# pca20054_sheet3_antenna_switches.net
KiCad netlist of a schematic drawn in Altium Designer
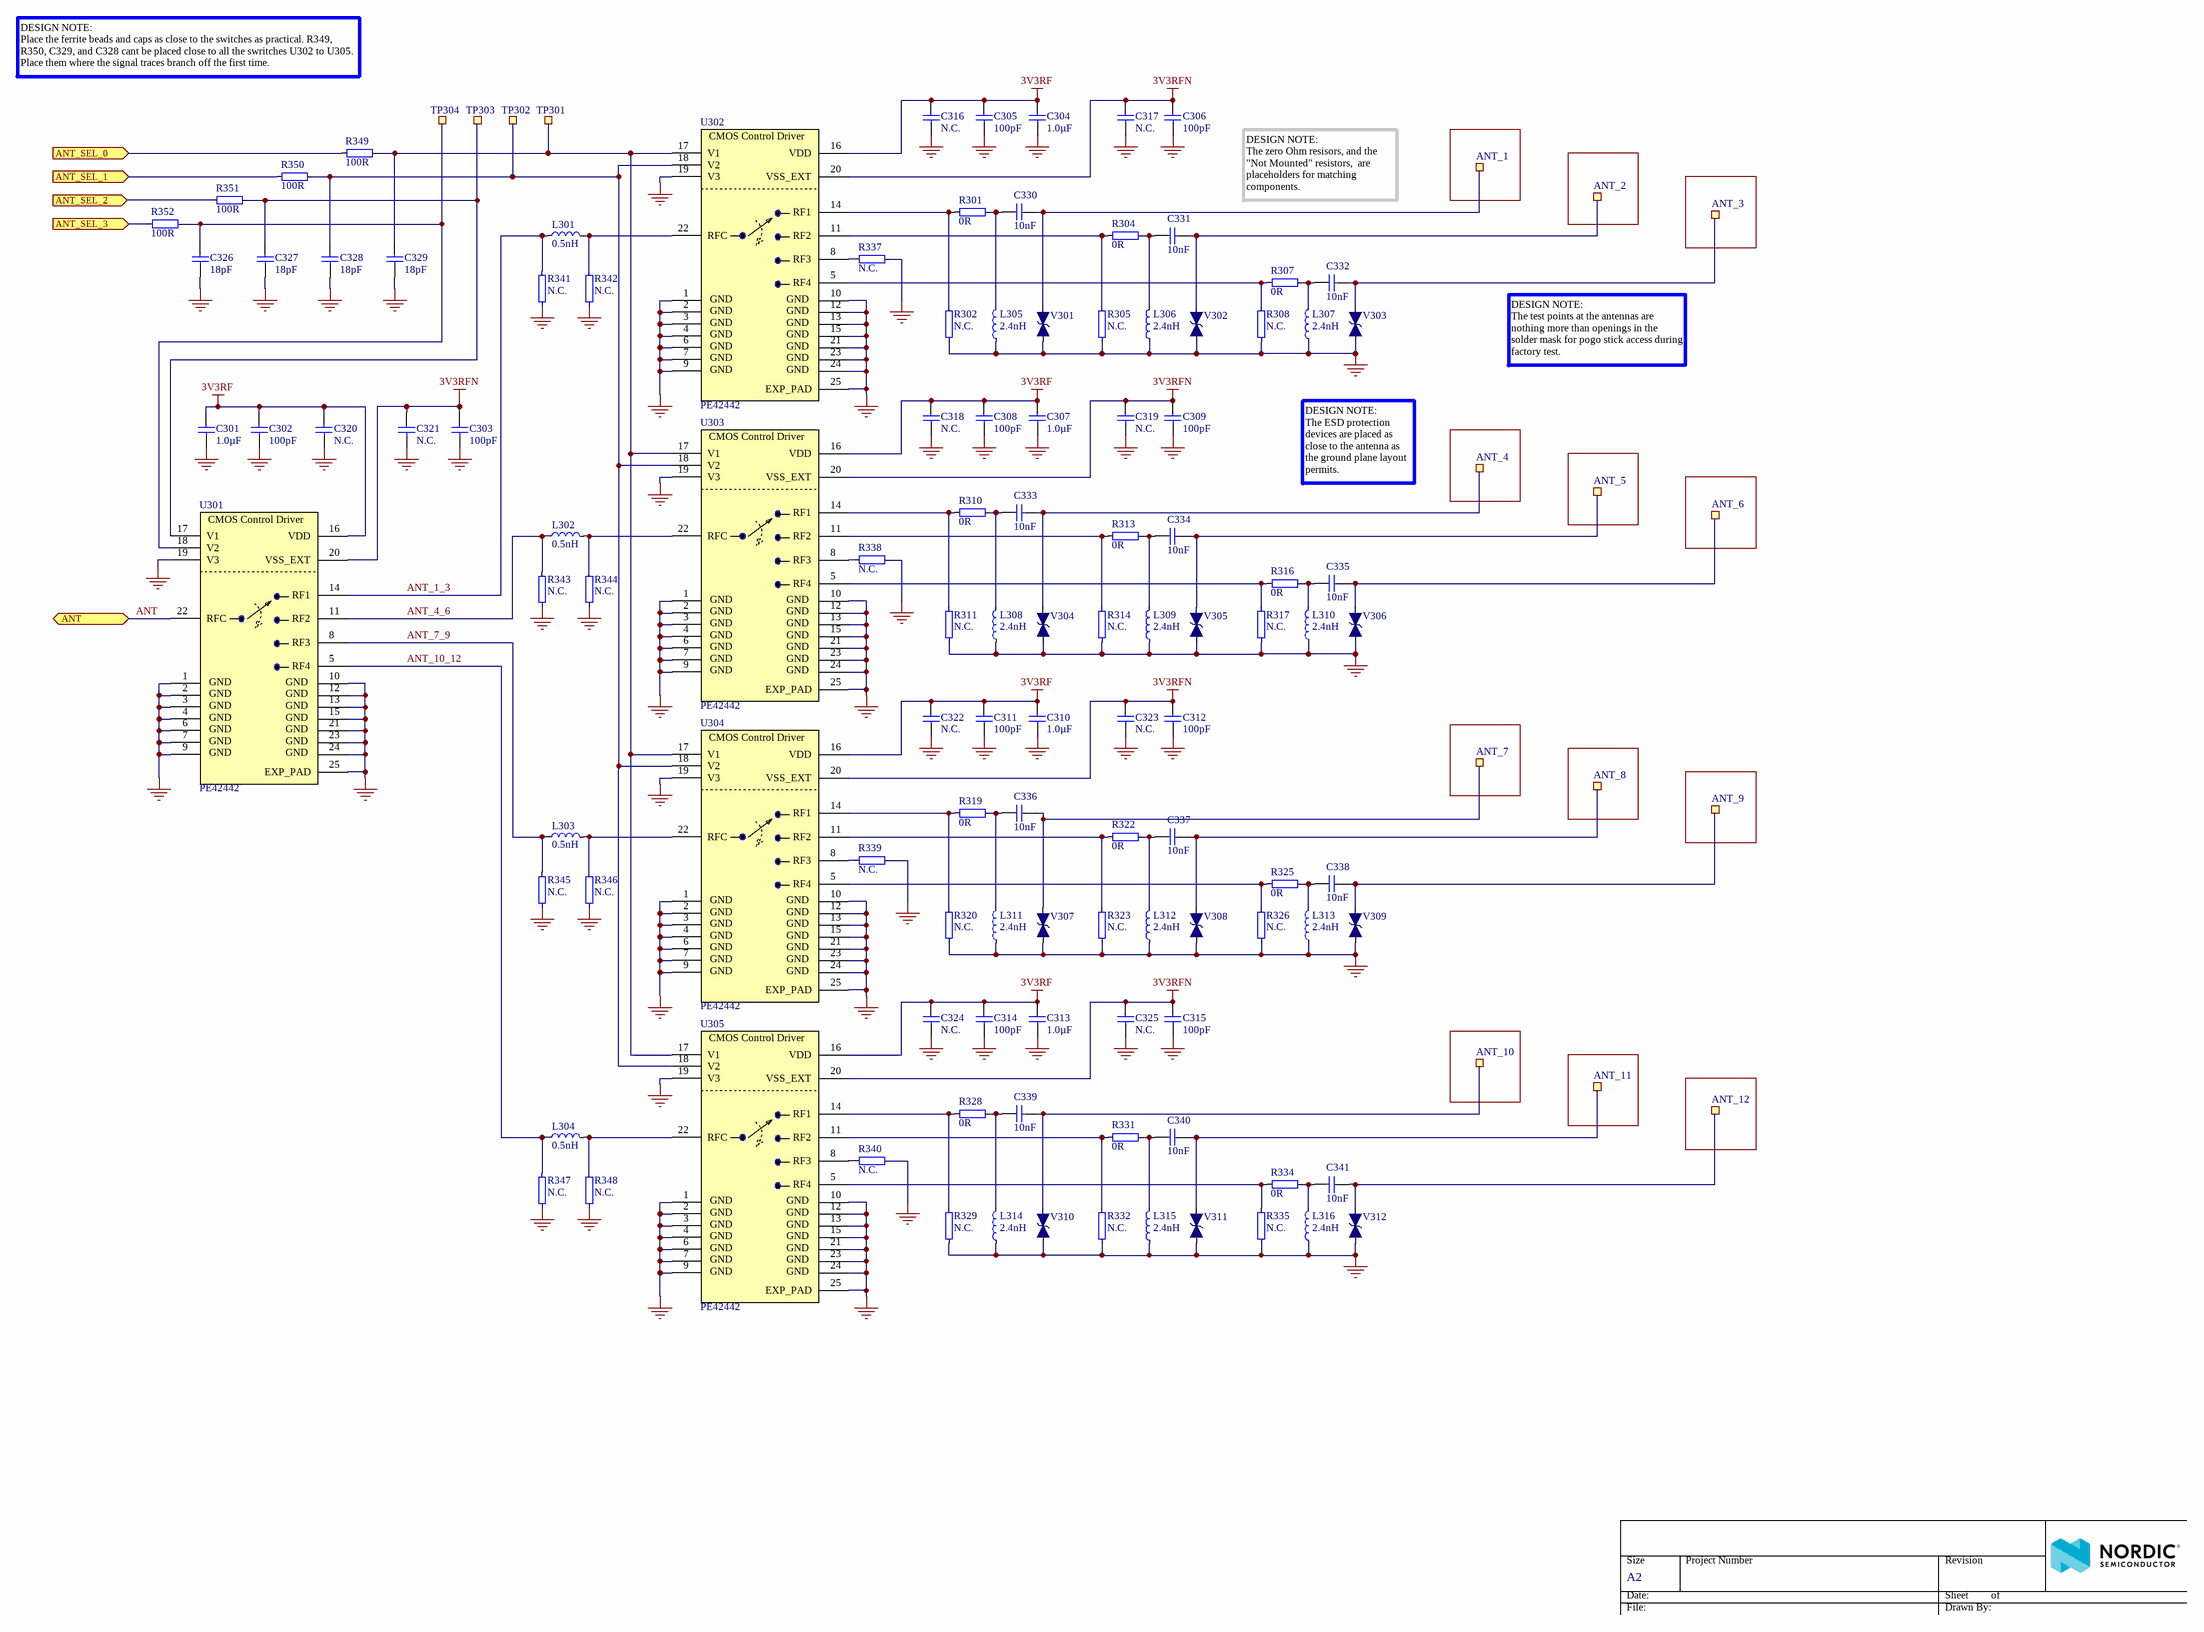
[diagram p0: pca20054_sheet3_antenna_switches.SchDoc]

(export (version "E")
  (design (tool "Eeschema 10.0.6"))
  (components
    (comp (ref "ANT_1")
      (value "Ø1.0mm,SMD")
      (footprint "TP_SMD_Ø1.0mm")
      (description "1.0mm circular SMD testpad")
      (fields
        (field (name "PART NUMBER") "TP_SMD_Ø1.0MM")
        (field (name "MANUFACTURER") "Nordic Semiconductor")
        (field (name "PUBLISHER") "Nordic Semiconductor")
      )
      (libsource (lib "Nordic Passive DB") (part "TESTPAD"))
    )
    (comp (ref "ANT_2")
      (value "Ø1.0mm,SMD")
      (footprint "TP_SMD_Ø1.0mm")
      (description "1.0mm circular SMD testpad")
      (fields
        (field (name "PART NUMBER") "TP_SMD_Ø1.0MM")
        (field (name "MANUFACTURER") "Nordic Semiconductor")
        (field (name "PUBLISHER") "Nordic Semiconductor")
      )
      (libsource (lib "Nordic Passive DB") (part "TESTPAD"))
    )
    (comp (ref "ANT_3")
      (value "Ø1.0mm,SMD")
      (footprint "TP_SMD_Ø1.0mm")
      (description "1.0mm circular SMD testpad")
      (fields
        (field (name "PART NUMBER") "TP_SMD_Ø1.0MM")
        (field (name "MANUFACTURER") "Nordic Semiconductor")
        (field (name "PUBLISHER") "Nordic Semiconductor")
      )
      (libsource (lib "Nordic Passive DB") (part "TESTPAD"))
    )
    (comp (ref "ANT_4")
      (value "Ø1.0mm,SMD")
      (footprint "TP_SMD_Ø1.0mm")
      (description "1.0mm circular SMD testpad")
      (fields
        (field (name "PART NUMBER") "TP_SMD_Ø1.0MM")
        (field (name "MANUFACTURER") "Nordic Semiconductor")
        (field (name "PUBLISHER") "Nordic Semiconductor")
      )
      (libsource (lib "Nordic Passive DB") (part "TESTPAD"))
    )
    (comp (ref "ANT_5")
      (value "Ø1.0mm,SMD")
      (footprint "TP_SMD_Ø1.0mm")
      (description "1.0mm circular SMD testpad")
      (fields
        (field (name "PART NUMBER") "TP_SMD_Ø1.0MM")
        (field (name "MANUFACTURER") "Nordic Semiconductor")
        (field (name "PUBLISHER") "Nordic Semiconductor")
      )
      (libsource (lib "Nordic Passive DB") (part "TESTPAD"))
    )
    (comp (ref "ANT_6")
      (value "Ø1.0mm,SMD")
      (footprint "TP_SMD_Ø1.0mm")
      (description "1.0mm circular SMD testpad")
      (fields
        (field (name "PART NUMBER") "TP_SMD_Ø1.0MM")
        (field (name "MANUFACTURER") "Nordic Semiconductor")
        (field (name "PUBLISHER") "Nordic Semiconductor")
      )
      (libsource (lib "Nordic Passive DB") (part "TESTPAD"))
    )
    (comp (ref "ANT_7")
      (value "Ø1.0mm,SMD")
      (footprint "TP_SMD_Ø1.0mm")
      (description "1.0mm circular SMD testpad")
      (fields
        (field (name "PART NUMBER") "TP_SMD_Ø1.0MM")
        (field (name "MANUFACTURER") "Nordic Semiconductor")
        (field (name "PUBLISHER") "Nordic Semiconductor")
      )
      (libsource (lib "Nordic Passive DB") (part "TESTPAD"))
    )
    (comp (ref "ANT_8")
      (value "Ø1.0mm,SMD")
      (footprint "TP_SMD_Ø1.0mm")
      (description "1.0mm circular SMD testpad")
      (fields
        (field (name "PART NUMBER") "TP_SMD_Ø1.0MM")
        (field (name "MANUFACTURER") "Nordic Semiconductor")
        (field (name "PUBLISHER") "Nordic Semiconductor")
      )
      (libsource (lib "Nordic Passive DB") (part "TESTPAD"))
    )
    (comp (ref "ANT_9")
      (value "Ø1.0mm,SMD")
      (footprint "TP_SMD_Ø1.0mm")
      (description "1.0mm circular SMD testpad")
      (fields
        (field (name "PART NUMBER") "TP_SMD_Ø1.0MM")
        (field (name "MANUFACTURER") "Nordic Semiconductor")
        (field (name "PUBLISHER") "Nordic Semiconductor")
      )
      (libsource (lib "Nordic Passive DB") (part "TESTPAD"))
    )
    (comp (ref "ANT_10")
      (value "Ø1.0mm,SMD")
      (footprint "TP_SMD_Ø1.0mm")
      (description "1.0mm circular SMD testpad")
      (fields
        (field (name "PART NUMBER") "TP_SMD_Ø1.0MM")
        (field (name "MANUFACTURER") "Nordic Semiconductor")
        (field (name "PUBLISHER") "Nordic Semiconductor")
      )
      (libsource (lib "Nordic Passive DB") (part "TESTPAD"))
    )
    (comp (ref "ANT_11")
      (value "Ø1.0mm,SMD")
      (footprint "TP_SMD_Ø1.0mm")
      (description "1.0mm circular SMD testpad")
      (fields
        (field (name "PART NUMBER") "TP_SMD_Ø1.0MM")
        (field (name "MANUFACTURER") "Nordic Semiconductor")
        (field (name "PUBLISHER") "Nordic Semiconductor")
      )
      (libsource (lib "Nordic Passive DB") (part "TESTPAD"))
    )
    (comp (ref "ANT_12")
      (value "Ø1.0mm,SMD")
      (footprint "TP_SMD_Ø1.0mm")
      (description "1.0mm circular SMD testpad")
      (fields
        (field (name "PART NUMBER") "TP_SMD_Ø1.0MM")
        (field (name "MANUFACTURER") "Nordic Semiconductor")
        (field (name "PUBLISHER") "Nordic Semiconductor")
      )
      (libsource (lib "Nordic Passive DB") (part "TESTPAD"))
    )
    (comp (ref "C301")
      (value "1.0µF")
      (footprint "CAPC1608X06L")
      (description "Capacitor, X7R, ±10%")
      (fields (field (name "PART NUMBER") "C0603-1µ0") (field (name "PUBLISHER") "Nordic Semiconductor"))
      (libsource (lib "Nordic Passive DB") (part "CAP"))
    )
    (comp (ref "C302")
      (value "100pF")
      (footprint "CAPC1005X04L")
      (description "Capacitor, NP0, ±5%")
      (fields (field (name "PART NUMBER") "C0402-100p") (field (name "PUBLISHER") "Nordic Semiconductor"))
      (libsource (lib "Nordic Passive DB") (part "CAP"))
    )
    (comp (ref "C303")
      (value "100pF")
      (footprint "CAPC1005X04L")
      (description "Capacitor, NP0, ±5%")
      (fields (field (name "PART NUMBER") "C0402-100p") (field (name "PUBLISHER") "Nordic Semiconductor"))
      (libsource (lib "Nordic Passive DB") (part "CAP"))
    )
    (comp (ref "C304")
      (value "1.0µF")
      (footprint "CAPC1608X06L")
      (description "Capacitor, X7R, ±10%")
      (fields (field (name "PART NUMBER") "C0603-1µ0") (field (name "PUBLISHER") "Nordic Semiconductor"))
      (libsource (lib "Nordic Passive DB") (part "CAP"))
    )
    (comp (ref "C305")
      (value "100pF")
      (footprint "CAPC1005X04L")
      (description "Capacitor, NP0, ±5%")
      (fields (field (name "PART NUMBER") "C0402-100p") (field (name "PUBLISHER") "Nordic Semiconductor"))
      (libsource (lib "Nordic Passive DB") (part "CAP"))
    )
    (comp (ref "C306")
      (value "100pF")
      (footprint "CAPC1005X04L")
      (description "Capacitor, NP0, ±5%")
      (fields (field (name "PART NUMBER") "C0402-100p") (field (name "PUBLISHER") "Nordic Semiconductor"))
      (libsource (lib "Nordic Passive DB") (part "CAP"))
    )
    (comp (ref "C307")
      (value "1.0µF")
      (footprint "CAPC1608X06L")
      (description "Capacitor, X7R, ±10%")
      (fields (field (name "PART NUMBER") "C0603-1µ0") (field (name "PUBLISHER") "Nordic Semiconductor"))
      (libsource (lib "Nordic Passive DB") (part "CAP"))
    )
    (comp (ref "C308")
      (value "100pF")
      (footprint "CAPC1005X04L")
      (description "Capacitor, NP0, ±5%")
      (fields (field (name "PART NUMBER") "C0402-100p") (field (name "PUBLISHER") "Nordic Semiconductor"))
      (libsource (lib "Nordic Passive DB") (part "CAP"))
    )
    (comp (ref "C309")
      (value "100pF")
      (footprint "CAPC1005X04L")
      (description "Capacitor, NP0, ±5%")
      (fields (field (name "PART NUMBER") "C0402-100p") (field (name "PUBLISHER") "Nordic Semiconductor"))
      (libsource (lib "Nordic Passive DB") (part "CAP"))
    )
    (comp (ref "C310")
      (value "1.0µF")
      (footprint "CAPC1608X06L")
      (description "Capacitor, X7R, ±10%")
      (fields (field (name "PART NUMBER") "C0603-1µ0") (field (name "PUBLISHER") "Nordic Semiconductor"))
      (libsource (lib "Nordic Passive DB") (part "CAP"))
    )
    (comp (ref "C311")
      (value "100pF")
      (footprint "CAPC1005X04L")
      (description "Capacitor, NP0, ±5%")
      (fields (field (name "PART NUMBER") "C0402-100p") (field (name "PUBLISHER") "Nordic Semiconductor"))
      (libsource (lib "Nordic Passive DB") (part "CAP"))
    )
    (comp (ref "C312")
      (value "100pF")
      (footprint "CAPC1005X04L")
      (description "Capacitor, NP0, ±5%")
      (fields (field (name "PART NUMBER") "C0402-100p") (field (name "PUBLISHER") "Nordic Semiconductor"))
      (libsource (lib "Nordic Passive DB") (part "CAP"))
    )
    (comp (ref "C313")
      (value "1.0µF")
      (footprint "CAPC1608X06L")
      (description "Capacitor, X7R, ±10%")
      (fields (field (name "PART NUMBER") "C0603-1µ0") (field (name "PUBLISHER") "Nordic Semiconductor"))
      (libsource (lib "Nordic Passive DB") (part "CAP"))
    )
    (comp (ref "C314")
      (value "100pF")
      (footprint "CAPC1005X04L")
      (description "Capacitor, NP0, ±5%")
      (fields (field (name "PART NUMBER") "C0402-100p") (field (name "PUBLISHER") "Nordic Semiconductor"))
      (libsource (lib "Nordic Passive DB") (part "CAP"))
    )
    (comp (ref "C315")
      (value "100pF")
      (footprint "CAPC1005X04L")
      (description "Capacitor, NP0, ±5%")
      (fields (field (name "PART NUMBER") "C0402-100p") (field (name "PUBLISHER") "Nordic Semiconductor"))
      (libsource (lib "Nordic Passive DB") (part "CAP"))
    )
    (comp (ref "C316")
      (value "N.C.")
      (footprint "CAPC1005X04L_NC")
      (description "Not mounted")
      (fields (field (name "PART NUMBER") "C0402-N.C.") (field (name "PUBLISHER") "Nordic Semiconductor"))
      (libsource (lib "Nordic Passive DB") (part "CAP"))
    )
    (comp (ref "C317")
      (value "N.C.")
      (footprint "CAPC1005X04L_NC")
      (description "Not mounted")
      (fields (field (name "PART NUMBER") "C0402-N.C.") (field (name "PUBLISHER") "Nordic Semiconductor"))
      (libsource (lib "Nordic Passive DB") (part "CAP"))
    )
    (comp (ref "C318")
      (value "N.C.")
      (footprint "CAPC1005X04L_NC")
      (description "Not mounted")
      (fields (field (name "PART NUMBER") "C0402-N.C.") (field (name "PUBLISHER") "Nordic Semiconductor"))
      (libsource (lib "Nordic Passive DB") (part "CAP"))
    )
    (comp (ref "C319")
      (value "N.C.")
      (footprint "CAPC1005X04L_NC")
      (description "Not mounted")
      (fields (field (name "PART NUMBER") "C0402-N.C.") (field (name "PUBLISHER") "Nordic Semiconductor"))
      (libsource (lib "Nordic Passive DB") (part "CAP"))
    )
    (comp (ref "C320")
      (value "N.C.")
      (footprint "CAPC1005X04L_NC")
      (description "Not mounted")
      (fields (field (name "PART NUMBER") "C0402-N.C.") (field (name "PUBLISHER") "Nordic Semiconductor"))
      (libsource (lib "Nordic Passive DB") (part "CAP"))
    )
    (comp (ref "C321")
      (value "N.C.")
      (footprint "CAPC1005X04L_NC")
      (description "Not mounted")
      (fields (field (name "PART NUMBER") "C0402-N.C.") (field (name "PUBLISHER") "Nordic Semiconductor"))
      (libsource (lib "Nordic Passive DB") (part "CAP"))
    )
    (comp (ref "C322")
      (value "N.C.")
      (footprint "CAPC1005X04L_NC")
      (description "Not mounted")
      (fields (field (name "PART NUMBER") "C0402-N.C.") (field (name "PUBLISHER") "Nordic Semiconductor"))
      (libsource (lib "Nordic Passive DB") (part "CAP"))
    )
    (comp (ref "C323")
      (value "N.C.")
      (footprint "CAPC1005X04L_NC")
      (description "Not mounted")
      (fields (field (name "PART NUMBER") "C0402-N.C.") (field (name "PUBLISHER") "Nordic Semiconductor"))
      (libsource (lib "Nordic Passive DB") (part "CAP"))
    )
    (comp (ref "C324")
      (value "N.C.")
      (footprint "CAPC1005X04L_NC")
      (description "Not mounted")
      (fields (field (name "PART NUMBER") "C0402-N.C.") (field (name "PUBLISHER") "Nordic Semiconductor"))
      (libsource (lib "Nordic Passive DB") (part "CAP"))
    )
    (comp (ref "C325")
      (value "N.C.")
      (footprint "CAPC1005X04L_NC")
      (description "Not mounted")
      (fields (field (name "PART NUMBER") "C0402-N.C.") (field (name "PUBLISHER") "Nordic Semiconductor"))
      (libsource (lib "Nordic Passive DB") (part "CAP"))
    )
    (comp (ref "C326")
      (value "18pF")
      (footprint "CAPC1005X04L")
      (description "Capacitor, NP0, ±5%")
      (fields (field (name "PART NUMBER") "C0402-18p") (field (name "PUBLISHER") "Nordic Semiconductor"))
      (libsource (lib "Nordic Passive DB") (part "CAP"))
    )
    (comp (ref "C327")
      (value "18pF")
      (footprint "CAPC1005X04L")
      (description "Capacitor, NP0, ±5%")
      (fields (field (name "PART NUMBER") "C0402-18p") (field (name "PUBLISHER") "Nordic Semiconductor"))
      (libsource (lib "Nordic Passive DB") (part "CAP"))
    )
    (comp (ref "C328")
      (value "18pF")
      (footprint "CAPC1005X04L")
      (description "Capacitor, NP0, ±5%")
      (fields (field (name "PART NUMBER") "C0402-18p") (field (name "PUBLISHER") "Nordic Semiconductor"))
      (libsource (lib "Nordic Passive DB") (part "CAP"))
    )
    (comp (ref "C329")
      (value "18pF")
      (footprint "CAPC1005X04L")
      (description "Capacitor, NP0, ±5%")
      (fields (field (name "PART NUMBER") "C0402-18p") (field (name "PUBLISHER") "Nordic Semiconductor"))
      (libsource (lib "Nordic Passive DB") (part "CAP"))
    )
    (comp (ref "C330")
      (value "10nF")
      (footprint "CAPC1005X04L")
      (description "Capacitor, X7R, ±10%")
      (fields (field (name "PART NUMBER") "C0402-10n") (field (name "PUBLISHER") "Nordic Semiconductor"))
      (libsource (lib "Nordic Passive DB") (part "CAP"))
    )
    (comp (ref "C331")
      (value "10nF")
      (footprint "CAPC1005X04L")
      (description "Capacitor, X7R, ±10%")
      (fields (field (name "PART NUMBER") "C0402-10n") (field (name "PUBLISHER") "Nordic Semiconductor"))
      (libsource (lib "Nordic Passive DB") (part "CAP"))
    )
    (comp (ref "C332")
      (value "10nF")
      (footprint "CAPC1005X04L")
      (description "Capacitor, X7R, ±10%")
      (fields (field (name "PART NUMBER") "C0402-10n") (field (name "PUBLISHER") "Nordic Semiconductor"))
      (libsource (lib "Nordic Passive DB") (part "CAP"))
    )
    (comp (ref "C333")
      (value "10nF")
      (footprint "CAPC1005X04L")
      (description "Capacitor, X7R, ±10%")
      (fields (field (name "PART NUMBER") "C0402-10n") (field (name "PUBLISHER") "Nordic Semiconductor"))
      (libsource (lib "Nordic Passive DB") (part "CAP"))
    )
    (comp (ref "C334")
      (value "10nF")
      (footprint "CAPC1005X04L")
      (description "Capacitor, X7R, ±10%")
      (fields (field (name "PART NUMBER") "C0402-10n") (field (name "PUBLISHER") "Nordic Semiconductor"))
      (libsource (lib "Nordic Passive DB") (part "CAP"))
    )
    (comp (ref "C335")
      (value "10nF")
      (footprint "CAPC1005X04L")
      (description "Capacitor, X7R, ±10%")
      (fields (field (name "PART NUMBER") "C0402-10n") (field (name "PUBLISHER") "Nordic Semiconductor"))
      (libsource (lib "Nordic Passive DB") (part "CAP"))
    )
    (comp (ref "C336")
      (value "10nF")
      (footprint "CAPC1005X04L")
      (description "Capacitor, X7R, ±10%")
      (fields (field (name "PART NUMBER") "C0402-10n") (field (name "PUBLISHER") "Nordic Semiconductor"))
      (libsource (lib "Nordic Passive DB") (part "CAP"))
    )
    (comp (ref "C337")
      (value "10nF")
      (footprint "CAPC1005X04L")
      (description "Capacitor, X7R, ±10%")
      (fields (field (name "PART NUMBER") "C0402-10n") (field (name "PUBLISHER") "Nordic Semiconductor"))
      (libsource (lib "Nordic Passive DB") (part "CAP"))
    )
    (comp (ref "C338")
      (value "10nF")
      (footprint "CAPC1005X04L")
      (description "Capacitor, X7R, ±10%")
      (fields (field (name "PART NUMBER") "C0402-10n") (field (name "PUBLISHER") "Nordic Semiconductor"))
      (libsource (lib "Nordic Passive DB") (part "CAP"))
    )
    (comp (ref "C339")
      (value "10nF")
      (footprint "CAPC1005X04L")
      (description "Capacitor, X7R, ±10%")
      (fields (field (name "PART NUMBER") "C0402-10n") (field (name "PUBLISHER") "Nordic Semiconductor"))
      (libsource (lib "Nordic Passive DB") (part "CAP"))
    )
    (comp (ref "C340")
      (value "10nF")
      (footprint "CAPC1005X04L")
      (description "Capacitor, X7R, ±10%")
      (fields (field (name "PART NUMBER") "C0402-10n") (field (name "PUBLISHER") "Nordic Semiconductor"))
      (libsource (lib "Nordic Passive DB") (part "CAP"))
    )
    (comp (ref "C341")
      (value "10nF")
      (footprint "CAPC1005X04L")
      (description "Capacitor, X7R, ±10%")
      (fields (field (name "PART NUMBER") "C0402-10n") (field (name "PUBLISHER") "Nordic Semiconductor"))
      (libsource (lib "Nordic Passive DB") (part "CAP"))
    )
    (comp (ref "L301")
      (value "0.5nH")
      (footprint "INDC1005X04L")
      (description "Inductor, 1A, ±0.1nH")
      (fields
        (field (name "PART NUMBER") "L0402-0n5")
        (field (name "MANUFACTURER") "TDK Corporation")
        (field (name "PUBLISHER") "Nordic Semiconductor")
      )
      (libsource (lib "Nordic Passive DB") (part "IND"))
    )
    (comp (ref "L302")
      (value "0.5nH")
      (footprint "INDC1005X04L")
      (description "Inductor, 1A, ±0.1nH")
      (fields
        (field (name "PART NUMBER") "L0402-0n5")
        (field (name "MANUFACTURER") "TDK Corporation")
        (field (name "PUBLISHER") "Nordic Semiconductor")
      )
      (libsource (lib "Nordic Passive DB") (part "IND"))
    )
    (comp (ref "L303")
      (value "0.5nH")
      (footprint "INDC1005X04L")
      (description "Inductor, 1A, ±0.1nH")
      (fields
        (field (name "PART NUMBER") "L0402-0n5")
        (field (name "MANUFACTURER") "TDK Corporation")
        (field (name "PUBLISHER") "Nordic Semiconductor")
      )
      (libsource (lib "Nordic Passive DB") (part "IND"))
    )
    (comp (ref "L304")
      (value "0.5nH")
      (footprint "INDC1005X04L")
      (description "Inductor, 1A, ±0.1nH")
      (fields
        (field (name "PART NUMBER") "L0402-0n5")
        (field (name "MANUFACTURER") "TDK Corporation")
        (field (name "PUBLISHER") "Nordic Semiconductor")
      )
      (libsource (lib "Nordic Passive DB") (part "IND"))
    )
    (comp (ref "L305")
      (value "2.4nH")
      (footprint "INDC1005X04L")
      (description "Inductor, 220mA, ±0.1nH")
      (fields (field (name "PART NUMBER") "L0402-2n4") (field (name "PUBLISHER") "Nordic Semiconductor"))
      (libsource (lib "Nordic Passive DB") (part "IND"))
    )
    (comp (ref "L306")
      (value "2.4nH")
      (footprint "INDC1005X04L")
      (description "Inductor, 220mA, ±0.1nH")
      (fields (field (name "PART NUMBER") "L0402-2n4") (field (name "PUBLISHER") "Nordic Semiconductor"))
      (libsource (lib "Nordic Passive DB") (part "IND"))
    )
    (comp (ref "L307")
      (value "2.4nH")
      (footprint "INDC1005X04L")
      (description "Inductor, 220mA, ±0.1nH")
      (fields (field (name "PART NUMBER") "L0402-2n4") (field (name "PUBLISHER") "Nordic Semiconductor"))
      (libsource (lib "Nordic Passive DB") (part "IND"))
    )
    (comp (ref "L308")
      (value "2.4nH")
      (footprint "INDC1005X04L")
      (description "Inductor, 220mA, ±0.1nH")
      (fields (field (name "PART NUMBER") "L0402-2n4") (field (name "PUBLISHER") "Nordic Semiconductor"))
      (libsource (lib "Nordic Passive DB") (part "IND"))
    )
    (comp (ref "L309")
      (value "2.4nH")
      (footprint "INDC1005X04L")
      (description "Inductor, 220mA, ±0.1nH")
      (fields (field (name "PART NUMBER") "L0402-2n4") (field (name "PUBLISHER") "Nordic Semiconductor"))
      (libsource (lib "Nordic Passive DB") (part "IND"))
    )
    (comp (ref "L310")
      (value "2.4nH")
      (footprint "INDC1005X04L")
      (description "Inductor, 220mA, ±0.1nH")
      (fields (field (name "PART NUMBER") "L0402-2n4") (field (name "PUBLISHER") "Nordic Semiconductor"))
      (libsource (lib "Nordic Passive DB") (part "IND"))
    )
    (comp (ref "L311")
      (value "2.4nH")
      (footprint "INDC1005X04L")
      (description "Inductor, 220mA, ±0.1nH")
      (fields (field (name "PART NUMBER") "L0402-2n4") (field (name "PUBLISHER") "Nordic Semiconductor"))
      (libsource (lib "Nordic Passive DB") (part "IND"))
    )
    (comp (ref "L312")
      (value "2.4nH")
      (footprint "INDC1005X04L")
      (description "Inductor, 220mA, ±0.1nH")
      (fields (field (name "PART NUMBER") "L0402-2n4") (field (name "PUBLISHER") "Nordic Semiconductor"))
      (libsource (lib "Nordic Passive DB") (part "IND"))
    )
    (comp (ref "L313")
      (value "2.4nH")
      (footprint "INDC1005X04L")
      (description "Inductor, 220mA, ±0.1nH")
      (fields (field (name "PART NUMBER") "L0402-2n4") (field (name "PUBLISHER") "Nordic Semiconductor"))
      (libsource (lib "Nordic Passive DB") (part "IND"))
    )
    (comp (ref "L314")
      (value "2.4nH")
      (footprint "INDC1005X04L")
      (description "Inductor, 220mA, ±0.1nH")
      (fields (field (name "PART NUMBER") "L0402-2n4") (field (name "PUBLISHER") "Nordic Semiconductor"))
      (libsource (lib "Nordic Passive DB") (part "IND"))
    )
    (comp (ref "L315")
      (value "2.4nH")
      (footprint "INDC1005X04L")
      (description "Inductor, 220mA, ±0.1nH")
      (fields (field (name "PART NUMBER") "L0402-2n4") (field (name "PUBLISHER") "Nordic Semiconductor"))
      (libsource (lib "Nordic Passive DB") (part "IND"))
    )
    (comp (ref "L316")
      (value "2.4nH")
      (footprint "INDC1005X04L")
      (description "Inductor, 220mA, ±0.1nH")
      (fields (field (name "PART NUMBER") "L0402-2n4") (field (name "PUBLISHER") "Nordic Semiconductor"))
      (libsource (lib "Nordic Passive DB") (part "IND"))
    )
    (comp (ref "R301")
      (value "0R")
      (footprint "RESC1005X04L")
      (description "Resistor, ±5%, 0.063W")
      (fields (field (name "PART NUMBER") "R0402-0R") (field (name "PUBLISHER") "Nordic Semiconductor"))
      (libsource (lib "Nordic Passive DB") (part "RES"))
    )
    (comp (ref "R302")
      (value "N.C.")
      (footprint "RESC1005X04L_NC")
      (description "Not mounted")
      (fields (field (name "PART NUMBER") "R0402-N.C.") (field (name "PUBLISHER") "Nordic Semiconductor"))
      (libsource (lib "Nordic Passive DB") (part "RES"))
    )
    (comp (ref "R304")
      (value "0R")
      (footprint "RESC1005X04L")
      (description "Resistor, ±5%, 0.063W")
      (fields (field (name "PART NUMBER") "R0402-0R") (field (name "PUBLISHER") "Nordic Semiconductor"))
      (libsource (lib "Nordic Passive DB") (part "RES"))
    )
    (comp (ref "R305")
      (value "N.C.")
      (footprint "RESC1005X04L_NC")
      (description "Not mounted")
      (fields (field (name "PART NUMBER") "R0402-N.C.") (field (name "PUBLISHER") "Nordic Semiconductor"))
      (libsource (lib "Nordic Passive DB") (part "RES"))
    )
    (comp (ref "R307")
      (value "0R")
      (footprint "RESC1005X04L")
      (description "Resistor, ±5%, 0.063W")
      (fields (field (name "PART NUMBER") "R0402-0R") (field (name "PUBLISHER") "Nordic Semiconductor"))
      (libsource (lib "Nordic Passive DB") (part "RES"))
    )
    (comp (ref "R308")
      (value "N.C.")
      (footprint "RESC1005X04L_NC")
      (description "Not mounted")
      (fields (field (name "PART NUMBER") "R0402-N.C.") (field (name "PUBLISHER") "Nordic Semiconductor"))
      (libsource (lib "Nordic Passive DB") (part "RES"))
    )
    (comp (ref "R310")
      (value "0R")
      (footprint "RESC1005X04L")
      (description "Resistor, ±5%, 0.063W")
      (fields (field (name "PART NUMBER") "R0402-0R") (field (name "PUBLISHER") "Nordic Semiconductor"))
      (libsource (lib "Nordic Passive DB") (part "RES"))
    )
    (comp (ref "R311")
      (value "N.C.")
      (footprint "RESC1005X04L_NC")
      (description "Not mounted")
      (fields (field (name "PART NUMBER") "R0402-N.C.") (field (name "PUBLISHER") "Nordic Semiconductor"))
      (libsource (lib "Nordic Passive DB") (part "RES"))
    )
    (comp (ref "R313")
      (value "0R")
      (footprint "RESC1005X04L")
      (description "Resistor, ±5%, 0.063W")
      (fields (field (name "PART NUMBER") "R0402-0R") (field (name "PUBLISHER") "Nordic Semiconductor"))
      (libsource (lib "Nordic Passive DB") (part "RES"))
    )
    (comp (ref "R314")
      (value "N.C.")
      (footprint "RESC1005X04L_NC")
      (description "Not mounted")
      (fields (field (name "PART NUMBER") "R0402-N.C.") (field (name "PUBLISHER") "Nordic Semiconductor"))
      (libsource (lib "Nordic Passive DB") (part "RES"))
    )
    (comp (ref "R316")
      (value "0R")
      (footprint "RESC1005X04L")
      (description "Resistor, ±5%, 0.063W")
      (fields (field (name "PART NUMBER") "R0402-0R") (field (name "PUBLISHER") "Nordic Semiconductor"))
      (libsource (lib "Nordic Passive DB") (part "RES"))
    )
    (comp (ref "R317")
      (value "N.C.")
      (footprint "RESC1005X04L_NC")
      (description "Not mounted")
      (fields (field (name "PART NUMBER") "R0402-N.C.") (field (name "PUBLISHER") "Nordic Semiconductor"))
      (libsource (lib "Nordic Passive DB") (part "RES"))
    )
    (comp (ref "R319")
      (value "0R")
      (footprint "RESC1005X04L")
      (description "Resistor, ±5%, 0.063W")
      (fields (field (name "PART NUMBER") "R0402-0R") (field (name "PUBLISHER") "Nordic Semiconductor"))
      (libsource (lib "Nordic Passive DB") (part "RES"))
    )
    (comp (ref "R320")
      (value "N.C.")
      (footprint "RESC1005X04L_NC")
      (description "Not mounted")
      (fields (field (name "PART NUMBER") "R0402-N.C.") (field (name "PUBLISHER") "Nordic Semiconductor"))
      (libsource (lib "Nordic Passive DB") (part "RES"))
    )
    (comp (ref "R322")
      (value "0R")
      (footprint "RESC1005X04L")
      (description "Resistor, ±5%, 0.063W")
      (fields (field (name "PART NUMBER") "R0402-0R") (field (name "PUBLISHER") "Nordic Semiconductor"))
      (libsource (lib "Nordic Passive DB") (part "RES"))
    )
    (comp (ref "R323")
      (value "N.C.")
      (footprint "RESC1005X04L_NC")
      (description "Not mounted")
      (fields (field (name "PART NUMBER") "R0402-N.C.") (field (name "PUBLISHER") "Nordic Semiconductor"))
      (libsource (lib "Nordic Passive DB") (part "RES"))
    )
    (comp (ref "R325")
      (value "0R")
      (footprint "RESC1005X04L")
      (description "Resistor, ±5%, 0.063W")
      (fields (field (name "PART NUMBER") "R0402-0R") (field (name "PUBLISHER") "Nordic Semiconductor"))
      (libsource (lib "Nordic Passive DB") (part "RES"))
    )
    (comp (ref "R326")
      (value "N.C.")
      (footprint "RESC1005X04L_NC")
      (description "Not mounted")
      (fields (field (name "PART NUMBER") "R0402-N.C.") (field (name "PUBLISHER") "Nordic Semiconductor"))
      (libsource (lib "Nordic Passive DB") (part "RES"))
    )
    (comp (ref "R328")
      (value "0R")
      (footprint "RESC1005X04L")
      (description "Resistor, ±5%, 0.063W")
      (fields (field (name "PART NUMBER") "R0402-0R") (field (name "PUBLISHER") "Nordic Semiconductor"))
      (libsource (lib "Nordic Passive DB") (part "RES"))
    )
    (comp (ref "R329")
      (value "N.C.")
      (footprint "RESC1005X04L_NC")
      (description "Not mounted")
      (fields (field (name "PART NUMBER") "R0402-N.C.") (field (name "PUBLISHER") "Nordic Semiconductor"))
      (libsource (lib "Nordic Passive DB") (part "RES"))
    )
    (comp (ref "R331")
      (value "0R")
      (footprint "RESC1005X04L")
      (description "Resistor, ±5%, 0.063W")
      (fields (field (name "PART NUMBER") "R0402-0R") (field (name "PUBLISHER") "Nordic Semiconductor"))
      (libsource (lib "Nordic Passive DB") (part "RES"))
    )
    (comp (ref "R332")
      (value "N.C.")
      (footprint "RESC1005X04L_NC")
      (description "Not mounted")
      (fields (field (name "PART NUMBER") "R0402-N.C.") (field (name "PUBLISHER") "Nordic Semiconductor"))
      (libsource (lib "Nordic Passive DB") (part "RES"))
    )
    (comp (ref "R334")
      (value "0R")
      (footprint "RESC1005X04L")
      (description "Resistor, ±5%, 0.063W")
      (fields (field (name "PART NUMBER") "R0402-0R") (field (name "PUBLISHER") "Nordic Semiconductor"))
      (libsource (lib "Nordic Passive DB") (part "RES"))
    )
    (comp (ref "R335")
      (value "N.C.")
      (footprint "RESC1005X04L_NC")
      (description "Not mounted")
      (fields (field (name "PART NUMBER") "R0402-N.C.") (field (name "PUBLISHER") "Nordic Semiconductor"))
      (libsource (lib "Nordic Passive DB") (part "RES"))
    )
    (comp (ref "R337")
      (value "N.C.")
      (footprint "RESC1005X04L_NC")
      (description "Not mounted")
      (fields (field (name "PART NUMBER") "R0402-N.C.") (field (name "PUBLISHER") "Nordic Semiconductor"))
      (libsource (lib "Nordic Passive DB") (part "RES"))
    )
    (comp (ref "R338")
      (value "N.C.")
      (footprint "RESC1005X04L_NC")
      (description "Not mounted")
      (fields (field (name "PART NUMBER") "R0402-N.C.") (field (name "PUBLISHER") "Nordic Semiconductor"))
      (libsource (lib "Nordic Passive DB") (part "RES"))
    )
    (comp (ref "R339")
      (value "N.C.")
      (footprint "RESC1005X04L_NC")
      (description "Not mounted")
      (fields (field (name "PART NUMBER") "R0402-N.C.") (field (name "PUBLISHER") "Nordic Semiconductor"))
      (libsource (lib "Nordic Passive DB") (part "RES"))
    )
    (comp (ref "R340")
      (value "N.C.")
      (footprint "RESC1005X04L_NC")
      (description "Not mounted")
      (fields (field (name "PART NUMBER") "R0402-N.C.") (field (name "PUBLISHER") "Nordic Semiconductor"))
      (libsource (lib "Nordic Passive DB") (part "RES"))
    )
    (comp (ref "R341")
      (value "N.C.")
      (footprint "RESC1005X04L_NC")
      (description "Not mounted")
      (fields (field (name "PART NUMBER") "R0402-N.C.") (field (name "PUBLISHER") "Nordic Semiconductor"))
      (libsource (lib "Nordic Passive DB") (part "RES"))
    )
    (comp (ref "R342")
      (value "N.C.")
      (footprint "RESC1005X04L_NC")
      (description "Not mounted")
      (fields (field (name "PART NUMBER") "R0402-N.C.") (field (name "PUBLISHER") "Nordic Semiconductor"))
      (libsource (lib "Nordic Passive DB") (part "RES"))
    )
    (comp (ref "R343")
      (value "N.C.")
      (footprint "RESC1005X04L_NC")
      (description "Not mounted")
      (fields (field (name "PART NUMBER") "R0402-N.C.") (field (name "PUBLISHER") "Nordic Semiconductor"))
      (libsource (lib "Nordic Passive DB") (part "RES"))
    )
    (comp (ref "R344")
      (value "N.C.")
      (footprint "RESC1005X04L_NC")
      (description "Not mounted")
      (fields (field (name "PART NUMBER") "R0402-N.C.") (field (name "PUBLISHER") "Nordic Semiconductor"))
      (libsource (lib "Nordic Passive DB") (part "RES"))
    )
    (comp (ref "R345")
      (value "N.C.")
      (footprint "RESC1005X04L_NC")
      (description "Not mounted")
      (fields (field (name "PART NUMBER") "R0402-N.C.") (field (name "PUBLISHER") "Nordic Semiconductor"))
      (libsource (lib "Nordic Passive DB") (part "RES"))
    )
    (comp (ref "R346")
      (value "N.C.")
      (footprint "RESC1005X04L_NC")
      (description "Not mounted")
      (fields (field (name "PART NUMBER") "R0402-N.C.") (field (name "PUBLISHER") "Nordic Semiconductor"))
      (libsource (lib "Nordic Passive DB") (part "RES"))
    )
    (comp (ref "R347")
      (value "N.C.")
      (footprint "RESC1005X04L_NC")
      (description "Not mounted")
      (fields (field (name "PART NUMBER") "R0402-N.C.") (field (name "PUBLISHER") "Nordic Semiconductor"))
      (libsource (lib "Nordic Passive DB") (part "RES"))
    )
    (comp (ref "R348")
      (value "N.C.")
      (footprint "RESC1005X04L_NC")
      (description "Not mounted")
      (fields (field (name "PART NUMBER") "R0402-N.C.") (field (name "PUBLISHER") "Nordic Semiconductor"))
      (libsource (lib "Nordic Passive DB") (part "RES"))
    )
    (comp (ref "R349")
      (value "100R")
      (footprint "RESC1005X04L")
      (description "Resistor, ±1%, 0.063W")
      (fields (field (name "PART NUMBER") "R0402-100") (field (name "PUBLISHER") "Nordic Semiconductor"))
      (libsource (lib "Nordic Passive DB") (part "RES"))
    )
    (comp (ref "R350")
      (value "100R")
      (footprint "RESC1005X04L")
      (description "Resistor, ±1%, 0.063W")
      (fields (field (name "PART NUMBER") "R0402-100") (field (name "PUBLISHER") "Nordic Semiconductor"))
      (libsource (lib "Nordic Passive DB") (part "RES"))
    )
    (comp (ref "R351")
      (value "100R")
      (footprint "RESC1005X04L")
      (description "Resistor, ±1%, 0.063W")
      (fields (field (name "PART NUMBER") "R0402-100") (field (name "PUBLISHER") "Nordic Semiconductor"))
      (libsource (lib "Nordic Passive DB") (part "RES"))
    )
    (comp (ref "R352")
      (value "100R")
      (footprint "RESC1005X04L")
      (description "Resistor, ±1%, 0.063W")
      (fields (field (name "PART NUMBER") "R0402-100") (field (name "PUBLISHER") "Nordic Semiconductor"))
      (libsource (lib "Nordic Passive DB") (part "RES"))
    )
    (comp (ref "TP301")
      (value "Ø1.0mm,SMD")
      (footprint "TP_SMD_Ø1.0mm")
      (description "1.0mm circular SMD testpad")
      (fields
        (field (name "PART NUMBER") "TP_SMD_Ø1.0MM")
        (field (name "MANUFACTURER") "Nordic Semiconductor")
        (field (name "PUBLISHER") "Nordic Semiconductor")
      )
      (libsource (lib "Nordic Passive DB") (part "TESTPAD"))
    )
    (comp (ref "TP302")
      (value "Ø1.0mm,SMD")
      (footprint "TP_SMD_Ø1.0mm")
      (description "1.0mm circular SMD testpad")
      (fields
        (field (name "PART NUMBER") "TP_SMD_Ø1.0MM")
        (field (name "MANUFACTURER") "Nordic Semiconductor")
        (field (name "PUBLISHER") "Nordic Semiconductor")
      )
      (libsource (lib "Nordic Passive DB") (part "TESTPAD"))
    )
    (comp (ref "TP303")
      (value "Ø1.0mm,SMD")
      (footprint "TP_SMD_Ø1.0mm")
      (description "1.0mm circular SMD testpad")
      (fields
        (field (name "PART NUMBER") "TP_SMD_Ø1.0MM")
        (field (name "MANUFACTURER") "Nordic Semiconductor")
        (field (name "PUBLISHER") "Nordic Semiconductor")
      )
      (libsource (lib "Nordic Passive DB") (part "TESTPAD"))
    )
    (comp (ref "TP304")
      (value "Ø1.0mm,SMD")
      (footprint "TP_SMD_Ø1.0mm")
      (description "1.0mm circular SMD testpad")
      (fields
        (field (name "PART NUMBER") "TP_SMD_Ø1.0MM")
        (field (name "MANUFACTURER") "Nordic Semiconductor")
        (field (name "PUBLISHER") "Nordic Semiconductor")
      )
      (libsource (lib "Nordic Passive DB") (part "TESTPAD"))
    )
    (comp (ref "U301")
      (value "PE42442")
      (footprint "QFN50P400X400X80_HS-25N")
      (description "UltraCMOS SP4T RF Switch 30 MHz-6 GHz")
      (fields
        (field (name "MANUFACTURER") "Peregrine Semiconductors")
        (field (name "PUBLISHER") "Nordic Semiconductor")
      )
      (libsource (lib "Nordic Active DB") (part "PE42442"))
    )
    (comp (ref "U302")
      (value "PE42442")
      (footprint "QFN50P400X400X80_HS-25N")
      (description "UltraCMOS SP4T RF Switch 30 MHz-6 GHz")
      (fields
        (field (name "MANUFACTURER") "Peregrine Semiconductors")
        (field (name "PUBLISHER") "Nordic Semiconductor")
      )
      (libsource (lib "Nordic Active DB") (part "PE42442"))
    )
    (comp (ref "U303")
      (value "PE42442")
      (footprint "QFN50P400X400X80_HS-25N")
      (description "UltraCMOS SP4T RF Switch 30 MHz-6 GHz")
      (fields
        (field (name "MANUFACTURER") "Peregrine Semiconductors")
        (field (name "PUBLISHER") "Nordic Semiconductor")
      )
      (libsource (lib "Nordic Active DB") (part "PE42442"))
    )
    (comp (ref "U304")
      (value "PE42442")
      (footprint "QFN50P400X400X80_HS-25N")
      (description "UltraCMOS SP4T RF Switch 30 MHz-6 GHz")
      (fields
        (field (name "MANUFACTURER") "Peregrine Semiconductors")
        (field (name "PUBLISHER") "Nordic Semiconductor")
      )
      (libsource (lib "Nordic Active DB") (part "PE42442"))
    )
    (comp (ref "U305")
      (value "PE42442")
      (footprint "QFN50P400X400X80_HS-25N")
      (description "UltraCMOS SP4T RF Switch 30 MHz-6 GHz")
      (fields
        (field (name "MANUFACTURER") "Peregrine Semiconductors")
        (field (name "PUBLISHER") "Nordic Semiconductor")
      )
      (libsource (lib "Nordic Active DB") (part "PE42442"))
    )
    (comp (ref "V301")
      (value "LXES15AAA1-133")
      (footprint "RESC1005X04L")
      (description "TVS DIODE 15VWM 0402")
      (fields (field (name "MANUFACTURER") "Murata") (field (name "PUBLISHER") "Nordic Semiconductor"))
      (libsource (lib "Nordic Discrete DB") (part "D{colon}SUPP"))
    )
    (comp (ref "V302")
      (value "LXES15AAA1-133")
      (footprint "RESC1005X04L")
      (description "TVS DIODE 15VWM 0402")
      (fields (field (name "MANUFACTURER") "Murata") (field (name "PUBLISHER") "Nordic Semiconductor"))
      (libsource (lib "Nordic Discrete DB") (part "D{colon}SUPP"))
    )
    (comp (ref "V303")
      (value "LXES15AAA1-133")
      (footprint "RESC1005X04L")
      (description "TVS DIODE 15VWM 0402")
      (fields (field (name "MANUFACTURER") "Murata") (field (name "PUBLISHER") "Nordic Semiconductor"))
      (libsource (lib "Nordic Discrete DB") (part "D{colon}SUPP"))
    )
    (comp (ref "V304")
      (value "LXES15AAA1-133")
      (footprint "RESC1005X04L")
      (description "TVS DIODE 15VWM 0402")
      (fields (field (name "MANUFACTURER") "Murata") (field (name "PUBLISHER") "Nordic Semiconductor"))
      (libsource (lib "Nordic Discrete DB") (part "D{colon}SUPP"))
    )
    (comp (ref "V305")
      (value "LXES15AAA1-133")
      (footprint "RESC1005X04L")
      (description "TVS DIODE 15VWM 0402")
      (fields (field (name "MANUFACTURER") "Murata") (field (name "PUBLISHER") "Nordic Semiconductor"))
      (libsource (lib "Nordic Discrete DB") (part "D{colon}SUPP"))
    )
    (comp (ref "V306")
      (value "LXES15AAA1-133")
      (footprint "RESC1005X04L")
      (description "TVS DIODE 15VWM 0402")
      (fields (field (name "MANUFACTURER") "Murata") (field (name "PUBLISHER") "Nordic Semiconductor"))
      (libsource (lib "Nordic Discrete DB") (part "D{colon}SUPP"))
    )
    (comp (ref "V307")
      (value "LXES15AAA1-133")
      (footprint "RESC1005X04L")
      (description "TVS DIODE 15VWM 0402")
      (fields (field (name "MANUFACTURER") "Murata") (field (name "PUBLISHER") "Nordic Semiconductor"))
      (libsource (lib "Nordic Discrete DB") (part "D{colon}SUPP"))
    )
    (comp (ref "V308")
      (value "LXES15AAA1-133")
      (footprint "RESC1005X04L")
      (description "TVS DIODE 15VWM 0402")
      (fields (field (name "MANUFACTURER") "Murata") (field (name "PUBLISHER") "Nordic Semiconductor"))
      (libsource (lib "Nordic Discrete DB") (part "D{colon}SUPP"))
    )
    (comp (ref "V309")
      (value "LXES15AAA1-133")
      (footprint "RESC1005X04L")
      (description "TVS DIODE 15VWM 0402")
      (fields (field (name "MANUFACTURER") "Murata") (field (name "PUBLISHER") "Nordic Semiconductor"))
      (libsource (lib "Nordic Discrete DB") (part "D{colon}SUPP"))
    )
    (comp (ref "V310")
      (value "LXES15AAA1-133")
      (footprint "RESC1005X04L")
      (description "TVS DIODE 15VWM 0402")
      (fields (field (name "MANUFACTURER") "Murata") (field (name "PUBLISHER") "Nordic Semiconductor"))
      (libsource (lib "Nordic Discrete DB") (part "D{colon}SUPP"))
    )
    (comp (ref "V311")
      (value "LXES15AAA1-133")
      (footprint "RESC1005X04L")
      (description "TVS DIODE 15VWM 0402")
      (fields (field (name "MANUFACTURER") "Murata") (field (name "PUBLISHER") "Nordic Semiconductor"))
      (libsource (lib "Nordic Discrete DB") (part "D{colon}SUPP"))
    )
    (comp (ref "V312")
      (value "LXES15AAA1-133")
      (footprint "RESC1005X04L")
      (description "TVS DIODE 15VWM 0402")
      (fields (field (name "MANUFACTURER") "Murata") (field (name "PUBLISHER") "Nordic Semiconductor"))
      (libsource (lib "Nordic Discrete DB") (part "D{colon}SUPP"))
    )
  )
  (nets
    (net (code "1") (name "/ANT") (class "Default")
      (node (ref "U301") (pin "22") (pinfunction "RFC_22") (pintype "passive"))
    )
    (net (code "2") (name "/ANT_1_3") (class "Default")
      (node (ref "L301") (pin "1") (pinfunction "1_1") (pintype "passive"))
      (node (ref "R341") (pin "2") (pinfunction "2_2") (pintype "passive"))
      (node (ref "U301") (pin "14") (pinfunction "RF1_14") (pintype "passive"))
    )
    (net (code "3") (name "/ANT_4_6") (class "Default")
      (node (ref "L302") (pin "1") (pinfunction "1_1") (pintype "passive"))
      (node (ref "R343") (pin "2") (pinfunction "2_2") (pintype "passive"))
      (node (ref "U301") (pin "11") (pinfunction "RF2_11") (pintype "passive"))
    )
    (net (code "4") (name "/ANT_7_9") (class "Default")
      (node (ref "L303") (pin "1") (pinfunction "1_1") (pintype "passive"))
      (node (ref "R345") (pin "2") (pinfunction "2_2") (pintype "passive"))
      (node (ref "U301") (pin "8") (pinfunction "RF3_8") (pintype "passive"))
    )
    (net (code "5") (name "/ANT_10_12") (class "Default")
      (node (ref "L304") (pin "1") (pinfunction "1_1") (pintype "passive"))
      (node (ref "R347") (pin "2") (pinfunction "2_2") (pintype "passive"))
      (node (ref "U301") (pin "5") (pinfunction "RF4_5") (pintype "passive"))
    )
    (net (code "6") (name "/ANT_SEL_0") (class "Default")
      (node (ref "R349") (pin "1") (pinfunction "1_1") (pintype "passive"))
    )
    (net (code "7") (name "/ANT_SEL_1") (class "Default")
      (node (ref "R350") (pin "1") (pinfunction "1_1") (pintype "passive"))
    )
    (net (code "8") (name "/ANT_SEL_2") (class "Default")
      (node (ref "R351") (pin "1") (pinfunction "1_1") (pintype "passive"))
    )
    (net (code "9") (name "/ANT_SEL_3") (class "Default")
      (node (ref "R352") (pin "1") (pinfunction "1_1") (pintype "passive"))
    )
    (net (code "10") (name "3V3RF") (class "Default")
      (node (ref "C301") (pin "2") (pinfunction "2_2") (pintype "passive"))
      (node (ref "C302") (pin "2") (pinfunction "2_2") (pintype "passive"))
      (node (ref "C304") (pin "2") (pinfunction "2_2") (pintype "passive"))
      (node (ref "C305") (pin "2") (pinfunction "2_2") (pintype "passive"))
      (node (ref "C307") (pin "2") (pinfunction "2_2") (pintype "passive"))
      (node (ref "C308") (pin "2") (pinfunction "2_2") (pintype "passive"))
      (node (ref "C310") (pin "2") (pinfunction "2_2") (pintype "passive"))
      (node (ref "C311") (pin "2") (pinfunction "2_2") (pintype "passive"))
      (node (ref "C313") (pin "2") (pinfunction "2_2") (pintype "passive"))
      (node (ref "C314") (pin "2") (pinfunction "2_2") (pintype "passive"))
      (node (ref "C316") (pin "2") (pinfunction "2_2") (pintype "passive"))
      (node (ref "C318") (pin "2") (pinfunction "2_2") (pintype "passive"))
      (node (ref "C320") (pin "2") (pinfunction "2_2") (pintype "passive"))
      (node (ref "C322") (pin "2") (pinfunction "2_2") (pintype "passive"))
      (node (ref "C324") (pin "2") (pinfunction "2_2") (pintype "passive"))
      (node (ref "U301") (pin "16") (pinfunction "VDD_16") (pintype "power_in"))
      (node (ref "U302") (pin "16") (pinfunction "VDD_16") (pintype "power_in"))
      (node (ref "U303") (pin "16") (pinfunction "VDD_16") (pintype "power_in"))
      (node (ref "U304") (pin "16") (pinfunction "VDD_16") (pintype "power_in"))
      (node (ref "U305") (pin "16") (pinfunction "VDD_16") (pintype "power_in"))
    )
    (net (code "11") (name "3V3RFN") (class "Default")
      (node (ref "C303") (pin "2") (pinfunction "2_2") (pintype "passive"))
      (node (ref "C306") (pin "2") (pinfunction "2_2") (pintype "passive"))
      (node (ref "C309") (pin "2") (pinfunction "2_2") (pintype "passive"))
      (node (ref "C312") (pin "2") (pinfunction "2_2") (pintype "passive"))
      (node (ref "C315") (pin "2") (pinfunction "2_2") (pintype "passive"))
      (node (ref "C317") (pin "2") (pinfunction "2_2") (pintype "passive"))
      (node (ref "C319") (pin "2") (pinfunction "2_2") (pintype "passive"))
      (node (ref "C321") (pin "2") (pinfunction "2_2") (pintype "passive"))
      (node (ref "C323") (pin "2") (pinfunction "2_2") (pintype "passive"))
      (node (ref "C325") (pin "2") (pinfunction "2_2") (pintype "passive"))
      (node (ref "U301") (pin "20") (pinfunction "VSS_EXT_20") (pintype "power_in"))
      (node (ref "U302") (pin "20") (pinfunction "VSS_EXT_20") (pintype "power_in"))
      (node (ref "U303") (pin "20") (pinfunction "VSS_EXT_20") (pintype "power_in"))
      (node (ref "U304") (pin "20") (pinfunction "VSS_EXT_20") (pintype "power_in"))
      (node (ref "U305") (pin "20") (pinfunction "VSS_EXT_20") (pintype "power_in"))
    )
    (net (code "12") (name "GND") (class "Default")
      (node (ref "C301") (pin "1") (pinfunction "1_1") (pintype "passive"))
      (node (ref "C302") (pin "1") (pinfunction "1_1") (pintype "passive"))
      (node (ref "C303") (pin "1") (pinfunction "1_1") (pintype "passive"))
      (node (ref "C304") (pin "1") (pinfunction "1_1") (pintype "passive"))
      (node (ref "C305") (pin "1") (pinfunction "1_1") (pintype "passive"))
      (node (ref "C306") (pin "1") (pinfunction "1_1") (pintype "passive"))
      (node (ref "C307") (pin "1") (pinfunction "1_1") (pintype "passive"))
      (node (ref "C308") (pin "1") (pinfunction "1_1") (pintype "passive"))
      (node (ref "C309") (pin "1") (pinfunction "1_1") (pintype "passive"))
      (node (ref "C310") (pin "1") (pinfunction "1_1") (pintype "passive"))
      (node (ref "C311") (pin "1") (pinfunction "1_1") (pintype "passive"))
      (node (ref "C312") (pin "1") (pinfunction "1_1") (pintype "passive"))
      (node (ref "C313") (pin "1") (pinfunction "1_1") (pintype "passive"))
      (node (ref "C314") (pin "1") (pinfunction "1_1") (pintype "passive"))
      (node (ref "C315") (pin "1") (pinfunction "1_1") (pintype "passive"))
      (node (ref "C316") (pin "1") (pinfunction "1_1") (pintype "passive"))
      (node (ref "C317") (pin "1") (pinfunction "1_1") (pintype "passive"))
      (node (ref "C318") (pin "1") (pinfunction "1_1") (pintype "passive"))
      (node (ref "C319") (pin "1") (pinfunction "1_1") (pintype "passive"))
      (node (ref "C320") (pin "1") (pinfunction "1_1") (pintype "passive"))
      (node (ref "C321") (pin "1") (pinfunction "1_1") (pintype "passive"))
      (node (ref "C322") (pin "1") (pinfunction "1_1") (pintype "passive"))
      (node (ref "C323") (pin "1") (pinfunction "1_1") (pintype "passive"))
      (node (ref "C324") (pin "1") (pinfunction "1_1") (pintype "passive"))
      (node (ref "C325") (pin "1") (pinfunction "1_1") (pintype "passive"))
      (node (ref "C326") (pin "1") (pinfunction "1_1") (pintype "passive"))
      (node (ref "C327") (pin "1") (pinfunction "1_1") (pintype "passive"))
      (node (ref "C328") (pin "1") (pinfunction "1_1") (pintype "passive"))
      (node (ref "C329") (pin "1") (pinfunction "1_1") (pintype "passive"))
      (node (ref "L305") (pin "1") (pinfunction "1_1") (pintype "passive"))
      (node (ref "L306") (pin "1") (pinfunction "1_1") (pintype "passive"))
      (node (ref "L307") (pin "1") (pinfunction "1_1") (pintype "passive"))
      (node (ref "L308") (pin "1") (pinfunction "1_1") (pintype "passive"))
      (node (ref "L309") (pin "1") (pinfunction "1_1") (pintype "passive"))
      (node (ref "L310") (pin "1") (pinfunction "1_1") (pintype "passive"))
      (node (ref "L311") (pin "1") (pinfunction "1_1") (pintype "passive"))
      (node (ref "L312") (pin "1") (pinfunction "1_1") (pintype "passive"))
      (node (ref "L313") (pin "1") (pinfunction "1_1") (pintype "passive"))
      (node (ref "L314") (pin "1") (pinfunction "1_1") (pintype "passive"))
      (node (ref "L315") (pin "1") (pinfunction "1_1") (pintype "passive"))
      (node (ref "L316") (pin "1") (pinfunction "1_1") (pintype "passive"))
      (node (ref "R302") (pin "1") (pinfunction "1_1") (pintype "passive"))
      (node (ref "R305") (pin "1") (pinfunction "1_1") (pintype "passive"))
      (node (ref "R308") (pin "1") (pinfunction "1_1") (pintype "passive"))
      (node (ref "R311") (pin "1") (pinfunction "1_1") (pintype "passive"))
      (node (ref "R314") (pin "1") (pinfunction "1_1") (pintype "passive"))
      (node (ref "R317") (pin "1") (pinfunction "1_1") (pintype "passive"))
      (node (ref "R320") (pin "1") (pinfunction "1_1") (pintype "passive"))
      (node (ref "R323") (pin "1") (pinfunction "1_1") (pintype "passive"))
      (node (ref "R326") (pin "1") (pinfunction "1_1") (pintype "passive"))
      (node (ref "R329") (pin "1") (pinfunction "1_1") (pintype "passive"))
      (node (ref "R332") (pin "1") (pinfunction "1_1") (pintype "passive"))
      (node (ref "R335") (pin "1") (pinfunction "1_1") (pintype "passive"))
      (node (ref "R337") (pin "2") (pinfunction "2_2") (pintype "passive"))
      (node (ref "R338") (pin "2") (pinfunction "2_2") (pintype "passive"))
      (node (ref "R339") (pin "2") (pinfunction "2_2") (pintype "passive"))
      (node (ref "R340") (pin "2") (pinfunction "2_2") (pintype "passive"))
      (node (ref "R341") (pin "1") (pinfunction "1_1") (pintype "passive"))
      (node (ref "R342") (pin "1") (pinfunction "1_1") (pintype "passive"))
      (node (ref "R343") (pin "1") (pinfunction "1_1") (pintype "passive"))
      (node (ref "R344") (pin "1") (pinfunction "1_1") (pintype "passive"))
      (node (ref "R345") (pin "1") (pinfunction "1_1") (pintype "passive"))
      (node (ref "R346") (pin "1") (pinfunction "1_1") (pintype "passive"))
      (node (ref "R347") (pin "1") (pinfunction "1_1") (pintype "passive"))
      (node (ref "R348") (pin "1") (pinfunction "1_1") (pintype "passive"))
      (node (ref "U301") (pin "1") (pinfunction "GND1_1") (pintype "power_in"))
      (node (ref "U301") (pin "10") (pinfunction "GND8_10") (pintype "power_in"))
      (node (ref "U301") (pin "12") (pinfunction "GND9_12") (pintype "power_in"))
      (node (ref "U301") (pin "13") (pinfunction "GND10_13") (pintype "power_in"))
      (node (ref "U301") (pin "15") (pinfunction "GND11_15") (pintype "power_in"))
      (node (ref "U301") (pin "19") (pinfunction "V3_19") (pintype "passive"))
      (node (ref "U301") (pin "2") (pinfunction "GND2_2") (pintype "power_in"))
      (node (ref "U301") (pin "21") (pinfunction "GND12_21") (pintype "power_in"))
      (node (ref "U301") (pin "23") (pinfunction "GND14_23") (pintype "power_in"))
      (node (ref "U301") (pin "24") (pinfunction "GND13_24") (pintype "power_in"))
      (node (ref "U301") (pin "25") (pinfunction "EXP_PAD_25") (pintype "power_in"))
      (node (ref "U301") (pin "3") (pinfunction "GND3_3") (pintype "power_in"))
      (node (ref "U301") (pin "4") (pinfunction "GND4_4") (pintype "power_in"))
      (node (ref "U301") (pin "6") (pinfunction "GND5_6") (pintype "power_in"))
      (node (ref "U301") (pin "7") (pinfunction "GND6_7") (pintype "power_in"))
      (node (ref "U301") (pin "9") (pinfunction "GND7_9") (pintype "power_in"))
      (node (ref "U302") (pin "1") (pinfunction "GND1_1") (pintype "power_in"))
      (node (ref "U302") (pin "10") (pinfunction "GND8_10") (pintype "power_in"))
      (node (ref "U302") (pin "12") (pinfunction "GND9_12") (pintype "power_in"))
      (node (ref "U302") (pin "13") (pinfunction "GND10_13") (pintype "power_in"))
      (node (ref "U302") (pin "15") (pinfunction "GND11_15") (pintype "power_in"))
      (node (ref "U302") (pin "19") (pinfunction "V3_19") (pintype "passive"))
      (node (ref "U302") (pin "2") (pinfunction "GND2_2") (pintype "power_in"))
      (node (ref "U302") (pin "21") (pinfunction "GND12_21") (pintype "power_in"))
      (node (ref "U302") (pin "23") (pinfunction "GND14_23") (pintype "power_in"))
      (node (ref "U302") (pin "24") (pinfunction "GND13_24") (pintype "power_in"))
      (node (ref "U302") (pin "25") (pinfunction "EXP_PAD_25") (pintype "power_in"))
      (node (ref "U302") (pin "3") (pinfunction "GND3_3") (pintype "power_in"))
      (node (ref "U302") (pin "4") (pinfunction "GND4_4") (pintype "power_in"))
      (node (ref "U302") (pin "6") (pinfunction "GND5_6") (pintype "power_in"))
      (node (ref "U302") (pin "7") (pinfunction "GND6_7") (pintype "power_in"))
      (node (ref "U302") (pin "9") (pinfunction "GND7_9") (pintype "power_in"))
      (node (ref "U303") (pin "1") (pinfunction "GND1_1") (pintype "power_in"))
      (node (ref "U303") (pin "10") (pinfunction "GND8_10") (pintype "power_in"))
      (node (ref "U303") (pin "12") (pinfunction "GND9_12") (pintype "power_in"))
      (node (ref "U303") (pin "13") (pinfunction "GND10_13") (pintype "power_in"))
      (node (ref "U303") (pin "15") (pinfunction "GND11_15") (pintype "power_in"))
      (node (ref "U303") (pin "19") (pinfunction "V3_19") (pintype "passive"))
      (node (ref "U303") (pin "2") (pinfunction "GND2_2") (pintype "power_in"))
      (node (ref "U303") (pin "21") (pinfunction "GND12_21") (pintype "power_in"))
      (node (ref "U303") (pin "23") (pinfunction "GND14_23") (pintype "power_in"))
      (node (ref "U303") (pin "24") (pinfunction "GND13_24") (pintype "power_in"))
      (node (ref "U303") (pin "25") (pinfunction "EXP_PAD_25") (pintype "power_in"))
      (node (ref "U303") (pin "3") (pinfunction "GND3_3") (pintype "power_in"))
      (node (ref "U303") (pin "4") (pinfunction "GND4_4") (pintype "power_in"))
      (node (ref "U303") (pin "6") (pinfunction "GND5_6") (pintype "power_in"))
      (node (ref "U303") (pin "7") (pinfunction "GND6_7") (pintype "power_in"))
      (node (ref "U303") (pin "9") (pinfunction "GND7_9") (pintype "power_in"))
      (node (ref "U304") (pin "1") (pinfunction "GND1_1") (pintype "power_in"))
      (node (ref "U304") (pin "10") (pinfunction "GND8_10") (pintype "power_in"))
      (node (ref "U304") (pin "12") (pinfunction "GND9_12") (pintype "power_in"))
      (node (ref "U304") (pin "13") (pinfunction "GND10_13") (pintype "power_in"))
      (node (ref "U304") (pin "15") (pinfunction "GND11_15") (pintype "power_in"))
      (node (ref "U304") (pin "19") (pinfunction "V3_19") (pintype "passive"))
      (node (ref "U304") (pin "2") (pinfunction "GND2_2") (pintype "power_in"))
      (node (ref "U304") (pin "21") (pinfunction "GND12_21") (pintype "power_in"))
      (node (ref "U304") (pin "23") (pinfunction "GND14_23") (pintype "power_in"))
      (node (ref "U304") (pin "24") (pinfunction "GND13_24") (pintype "power_in"))
      (node (ref "U304") (pin "25") (pinfunction "EXP_PAD_25") (pintype "power_in"))
      (node (ref "U304") (pin "3") (pinfunction "GND3_3") (pintype "power_in"))
      (node (ref "U304") (pin "4") (pinfunction "GND4_4") (pintype "power_in"))
      (node (ref "U304") (pin "6") (pinfunction "GND5_6") (pintype "power_in"))
      (node (ref "U304") (pin "7") (pinfunction "GND6_7") (pintype "power_in"))
      (node (ref "U304") (pin "9") (pinfunction "GND7_9") (pintype "power_in"))
      (node (ref "U305") (pin "1") (pinfunction "GND1_1") (pintype "power_in"))
      (node (ref "U305") (pin "10") (pinfunction "GND8_10") (pintype "power_in"))
      (node (ref "U305") (pin "12") (pinfunction "GND9_12") (pintype "power_in"))
      (node (ref "U305") (pin "13") (pinfunction "GND10_13") (pintype "power_in"))
      (node (ref "U305") (pin "15") (pinfunction "GND11_15") (pintype "power_in"))
      (node (ref "U305") (pin "19") (pinfunction "V3_19") (pintype "passive"))
      (node (ref "U305") (pin "2") (pinfunction "GND2_2") (pintype "power_in"))
      (node (ref "U305") (pin "21") (pinfunction "GND12_21") (pintype "power_in"))
      (node (ref "U305") (pin "23") (pinfunction "GND14_23") (pintype "power_in"))
      (node (ref "U305") (pin "24") (pinfunction "GND13_24") (pintype "power_in"))
      (node (ref "U305") (pin "25") (pinfunction "EXP_PAD_25") (pintype "power_in"))
      (node (ref "U305") (pin "3") (pinfunction "GND3_3") (pintype "power_in"))
      (node (ref "U305") (pin "4") (pinfunction "GND4_4") (pintype "power_in"))
      (node (ref "U305") (pin "6") (pinfunction "GND5_6") (pintype "power_in"))
      (node (ref "U305") (pin "7") (pinfunction "GND6_7") (pintype "power_in"))
      (node (ref "U305") (pin "9") (pinfunction "GND7_9") (pintype "power_in"))
      (node (ref "V301") (pin "2") (pintype "passive"))
      (node (ref "V302") (pin "2") (pintype "passive"))
      (node (ref "V303") (pin "2") (pintype "passive"))
      (node (ref "V304") (pin "2") (pintype "passive"))
      (node (ref "V305") (pin "2") (pintype "passive"))
      (node (ref "V306") (pin "2") (pintype "passive"))
      (node (ref "V307") (pin "2") (pintype "passive"))
      (node (ref "V308") (pin "2") (pintype "passive"))
      (node (ref "V309") (pin "2") (pintype "passive"))
      (node (ref "V310") (pin "2") (pintype "passive"))
      (node (ref "V311") (pin "2") (pintype "passive"))
      (node (ref "V312") (pin "2") (pintype "passive"))
    )
    (net (code "13") (name "Net-(ANT_1-Pad1)") (class "Default")
      (node (ref "ANT_1") (pin "1") (pinfunction "1_1") (pintype "passive"))
      (node (ref "C330") (pin "2") (pinfunction "2_2") (pintype "passive"))
      (node (ref "V301") (pin "1") (pintype "passive"))
    )
    (net (code "14") (name "Net-(ANT_2-Pad1)") (class "Default")
      (node (ref "ANT_2") (pin "1") (pinfunction "1_1") (pintype "passive"))
      (node (ref "C331") (pin "2") (pinfunction "2_2") (pintype "passive"))
      (node (ref "V302") (pin "1") (pintype "passive"))
    )
    (net (code "15") (name "Net-(ANT_3-Pad1)") (class "Default")
      (node (ref "ANT_3") (pin "1") (pinfunction "1_1") (pintype "passive"))
      (node (ref "C332") (pin "2") (pinfunction "2_2") (pintype "passive"))
      (node (ref "V303") (pin "1") (pintype "passive"))
    )
    (net (code "16") (name "Net-(ANT_4-Pad1)") (class "Default")
      (node (ref "ANT_4") (pin "1") (pinfunction "1_1") (pintype "passive"))
      (node (ref "C333") (pin "2") (pinfunction "2_2") (pintype "passive"))
      (node (ref "V304") (pin "1") (pintype "passive"))
    )
    (net (code "17") (name "Net-(ANT_5-Pad1)") (class "Default")
      (node (ref "ANT_5") (pin "1") (pinfunction "1_1") (pintype "passive"))
      (node (ref "C334") (pin "2") (pinfunction "2_2") (pintype "passive"))
      (node (ref "V305") (pin "1") (pintype "passive"))
    )
    (net (code "18") (name "Net-(ANT_6-Pad1)") (class "Default")
      (node (ref "ANT_6") (pin "1") (pinfunction "1_1") (pintype "passive"))
      (node (ref "C335") (pin "2") (pinfunction "2_2") (pintype "passive"))
      (node (ref "V306") (pin "1") (pintype "passive"))
    )
    (net (code "19") (name "Net-(ANT_7-Pad1)") (class "Default")
      (node (ref "ANT_7") (pin "1") (pinfunction "1_1") (pintype "passive"))
      (node (ref "C336") (pin "2") (pinfunction "2_2") (pintype "passive"))
      (node (ref "V307") (pin "1") (pintype "passive"))
    )
    (net (code "20") (name "Net-(ANT_8-Pad1)") (class "Default")
      (node (ref "ANT_8") (pin "1") (pinfunction "1_1") (pintype "passive"))
      (node (ref "C337") (pin "2") (pinfunction "2_2") (pintype "passive"))
      (node (ref "V308") (pin "1") (pintype "passive"))
    )
    (net (code "21") (name "Net-(ANT_9-Pad1)") (class "Default")
      (node (ref "ANT_9") (pin "1") (pinfunction "1_1") (pintype "passive"))
      (node (ref "C338") (pin "2") (pinfunction "2_2") (pintype "passive"))
      (node (ref "V309") (pin "1") (pintype "passive"))
    )
    (net (code "22") (name "Net-(ANT_10-Pad1)") (class "Default")
      (node (ref "ANT_10") (pin "1") (pinfunction "1_1") (pintype "passive"))
      (node (ref "C339") (pin "2") (pinfunction "2_2") (pintype "passive"))
      (node (ref "V310") (pin "1") (pintype "passive"))
    )
    (net (code "23") (name "Net-(ANT_11-Pad1)") (class "Default")
      (node (ref "ANT_11") (pin "1") (pinfunction "1_1") (pintype "passive"))
      (node (ref "C340") (pin "2") (pinfunction "2_2") (pintype "passive"))
      (node (ref "V311") (pin "1") (pintype "passive"))
    )
    (net (code "24") (name "Net-(ANT_12-Pad1)") (class "Default")
      (node (ref "ANT_12") (pin "1") (pinfunction "1_1") (pintype "passive"))
      (node (ref "C341") (pin "2") (pinfunction "2_2") (pintype "passive"))
      (node (ref "V312") (pin "1") (pintype "passive"))
    )
    (net (code "25") (name "Net-(C330-Pad1)") (class "Default")
      (node (ref "C330") (pin "1") (pinfunction "1_1") (pintype "passive"))
      (node (ref "L305") (pin "2") (pinfunction "2_2") (pintype "passive"))
      (node (ref "R301") (pin "2") (pinfunction "2_2") (pintype "passive"))
    )
    (net (code "26") (name "Net-(C331-Pad1)") (class "Default")
      (node (ref "C331") (pin "1") (pinfunction "1_1") (pintype "passive"))
      (node (ref "L306") (pin "2") (pinfunction "2_2") (pintype "passive"))
      (node (ref "R304") (pin "2") (pinfunction "2_2") (pintype "passive"))
    )
    (net (code "27") (name "Net-(C332-Pad1)") (class "Default")
      (node (ref "C332") (pin "1") (pinfunction "1_1") (pintype "passive"))
      (node (ref "L307") (pin "2") (pinfunction "2_2") (pintype "passive"))
      (node (ref "R307") (pin "2") (pinfunction "2_2") (pintype "passive"))
    )
    (net (code "28") (name "Net-(C333-Pad1)") (class "Default")
      (node (ref "C333") (pin "1") (pinfunction "1_1") (pintype "passive"))
      (node (ref "L308") (pin "2") (pinfunction "2_2") (pintype "passive"))
      (node (ref "R310") (pin "2") (pinfunction "2_2") (pintype "passive"))
    )
    (net (code "29") (name "Net-(C334-Pad1)") (class "Default")
      (node (ref "C334") (pin "1") (pinfunction "1_1") (pintype "passive"))
      (node (ref "L309") (pin "2") (pinfunction "2_2") (pintype "passive"))
      (node (ref "R313") (pin "2") (pinfunction "2_2") (pintype "passive"))
    )
    (net (code "30") (name "Net-(C335-Pad1)") (class "Default")
      (node (ref "C335") (pin "1") (pinfunction "1_1") (pintype "passive"))
      (node (ref "L310") (pin "2") (pinfunction "2_2") (pintype "passive"))
      (node (ref "R316") (pin "2") (pinfunction "2_2") (pintype "passive"))
    )
    (net (code "31") (name "Net-(C336-Pad1)") (class "Default")
      (node (ref "C336") (pin "1") (pinfunction "1_1") (pintype "passive"))
      (node (ref "L311") (pin "2") (pinfunction "2_2") (pintype "passive"))
      (node (ref "R319") (pin "2") (pinfunction "2_2") (pintype "passive"))
    )
    (net (code "32") (name "Net-(C337-Pad1)") (class "Default")
      (node (ref "C337") (pin "1") (pinfunction "1_1") (pintype "passive"))
      (node (ref "L312") (pin "2") (pinfunction "2_2") (pintype "passive"))
      (node (ref "R322") (pin "2") (pinfunction "2_2") (pintype "passive"))
    )
    (net (code "33") (name "Net-(C338-Pad1)") (class "Default")
      (node (ref "C338") (pin "1") (pinfunction "1_1") (pintype "passive"))
      (node (ref "L313") (pin "2") (pinfunction "2_2") (pintype "passive"))
      (node (ref "R325") (pin "2") (pinfunction "2_2") (pintype "passive"))
    )
    (net (code "34") (name "Net-(C339-Pad1)") (class "Default")
      (node (ref "C339") (pin "1") (pinfunction "1_1") (pintype "passive"))
      (node (ref "L314") (pin "2") (pinfunction "2_2") (pintype "passive"))
      (node (ref "R328") (pin "2") (pinfunction "2_2") (pintype "passive"))
    )
    (net (code "35") (name "Net-(C340-Pad1)") (class "Default")
      (node (ref "C340") (pin "1") (pinfunction "1_1") (pintype "passive"))
      (node (ref "L315") (pin "2") (pinfunction "2_2") (pintype "passive"))
      (node (ref "R331") (pin "2") (pinfunction "2_2") (pintype "passive"))
    )
    (net (code "36") (name "Net-(C341-Pad1)") (class "Default")
      (node (ref "C341") (pin "1") (pinfunction "1_1") (pintype "passive"))
      (node (ref "L316") (pin "2") (pinfunction "2_2") (pintype "passive"))
      (node (ref "R334") (pin "2") (pinfunction "2_2") (pintype "passive"))
    )
    (net (code "37") (name "Net-(U301-V1)") (class "Default")
      (node (ref "C327") (pin "2") (pinfunction "2_2") (pintype "passive"))
      (node (ref "R351") (pin "2") (pinfunction "2_2") (pintype "passive"))
      (node (ref "TP303") (pin "1") (pinfunction "1_1") (pintype "passive"))
      (node (ref "U301") (pin "17") (pinfunction "V1_17") (pintype "passive"))
    )
    (net (code "38") (name "Net-(U301-V2)") (class "Default")
      (node (ref "C326") (pin "2") (pinfunction "2_2") (pintype "passive"))
      (node (ref "R352") (pin "2") (pinfunction "2_2") (pintype "passive"))
      (node (ref "TP304") (pin "1") (pinfunction "1_1") (pintype "passive"))
      (node (ref "U301") (pin "18") (pinfunction "V2_18") (pintype "passive"))
    )
    (net (code "39") (name "Net-(U302-RF1)") (class "Default")
      (node (ref "R301") (pin "1") (pinfunction "1_1") (pintype "passive"))
      (node (ref "R302") (pin "2") (pinfunction "2_2") (pintype "passive"))
      (node (ref "U302") (pin "14") (pinfunction "RF1_14") (pintype "passive"))
    )
    (net (code "40") (name "Net-(U302-RF2)") (class "Default")
      (node (ref "R304") (pin "1") (pinfunction "1_1") (pintype "passive"))
      (node (ref "R305") (pin "2") (pinfunction "2_2") (pintype "passive"))
      (node (ref "U302") (pin "11") (pinfunction "RF2_11") (pintype "passive"))
    )
    (net (code "41") (name "Net-(U302-RF3)") (class "Default")
      (node (ref "R337") (pin "1") (pinfunction "1_1") (pintype "passive"))
      (node (ref "U302") (pin "8") (pinfunction "RF3_8") (pintype "passive"))
    )
    (net (code "42") (name "Net-(U302-RF4)") (class "Default")
      (node (ref "R307") (pin "1") (pinfunction "1_1") (pintype "passive"))
      (node (ref "R308") (pin "2") (pinfunction "2_2") (pintype "passive"))
      (node (ref "U302") (pin "5") (pinfunction "RF4_5") (pintype "passive"))
    )
    (net (code "43") (name "Net-(U302-RFC)") (class "Default")
      (node (ref "L301") (pin "2") (pinfunction "2_2") (pintype "passive"))
      (node (ref "R342") (pin "2") (pinfunction "2_2") (pintype "passive"))
      (node (ref "U302") (pin "22") (pinfunction "RFC_22") (pintype "passive"))
    )
    (net (code "44") (name "Net-(U302-V1)") (class "Default")
      (node (ref "C329") (pin "2") (pinfunction "2_2") (pintype "passive"))
      (node (ref "R349") (pin "2") (pinfunction "2_2") (pintype "passive"))
      (node (ref "TP301") (pin "1") (pinfunction "1_1") (pintype "passive"))
      (node (ref "U302") (pin "17") (pinfunction "V1_17") (pintype "passive"))
      (node (ref "U303") (pin "17") (pinfunction "V1_17") (pintype "passive"))
      (node (ref "U304") (pin "17") (pinfunction "V1_17") (pintype "passive"))
      (node (ref "U305") (pin "17") (pinfunction "V1_17") (pintype "passive"))
    )
    (net (code "45") (name "Net-(U302-V2)") (class "Default")
      (node (ref "C328") (pin "2") (pinfunction "2_2") (pintype "passive"))
      (node (ref "R350") (pin "2") (pinfunction "2_2") (pintype "passive"))
      (node (ref "TP302") (pin "1") (pinfunction "1_1") (pintype "passive"))
      (node (ref "U302") (pin "18") (pinfunction "V2_18") (pintype "passive"))
      (node (ref "U303") (pin "18") (pinfunction "V2_18") (pintype "passive"))
      (node (ref "U304") (pin "18") (pinfunction "V2_18") (pintype "passive"))
      (node (ref "U305") (pin "18") (pinfunction "V2_18") (pintype "passive"))
    )
    (net (code "46") (name "Net-(U303-RF1)") (class "Default")
      (node (ref "R310") (pin "1") (pinfunction "1_1") (pintype "passive"))
      (node (ref "R311") (pin "2") (pinfunction "2_2") (pintype "passive"))
      (node (ref "U303") (pin "14") (pinfunction "RF1_14") (pintype "passive"))
    )
    (net (code "47") (name "Net-(U303-RF2)") (class "Default")
      (node (ref "R313") (pin "1") (pinfunction "1_1") (pintype "passive"))
      (node (ref "R314") (pin "2") (pinfunction "2_2") (pintype "passive"))
      (node (ref "U303") (pin "11") (pinfunction "RF2_11") (pintype "passive"))
    )
    (net (code "48") (name "Net-(U303-RF3)") (class "Default")
      (node (ref "R338") (pin "1") (pinfunction "1_1") (pintype "passive"))
      (node (ref "U303") (pin "8") (pinfunction "RF3_8") (pintype "passive"))
    )
    (net (code "49") (name "Net-(U303-RF4)") (class "Default")
      (node (ref "R316") (pin "1") (pinfunction "1_1") (pintype "passive"))
      (node (ref "R317") (pin "2") (pinfunction "2_2") (pintype "passive"))
      (node (ref "U303") (pin "5") (pinfunction "RF4_5") (pintype "passive"))
    )
    (net (code "50") (name "Net-(U303-RFC)") (class "Default")
      (node (ref "L302") (pin "2") (pinfunction "2_2") (pintype "passive"))
      (node (ref "R344") (pin "2") (pinfunction "2_2") (pintype "passive"))
      (node (ref "U303") (pin "22") (pinfunction "RFC_22") (pintype "passive"))
    )
    (net (code "51") (name "Net-(U304-RF1)") (class "Default")
      (node (ref "R319") (pin "1") (pinfunction "1_1") (pintype "passive"))
      (node (ref "R320") (pin "2") (pinfunction "2_2") (pintype "passive"))
      (node (ref "U304") (pin "14") (pinfunction "RF1_14") (pintype "passive"))
    )
    (net (code "52") (name "Net-(U304-RF2)") (class "Default")
      (node (ref "R322") (pin "1") (pinfunction "1_1") (pintype "passive"))
      (node (ref "R323") (pin "2") (pinfunction "2_2") (pintype "passive"))
      (node (ref "U304") (pin "11") (pinfunction "RF2_11") (pintype "passive"))
    )
    (net (code "53") (name "Net-(U304-RF3)") (class "Default")
      (node (ref "R339") (pin "1") (pinfunction "1_1") (pintype "passive"))
      (node (ref "U304") (pin "8") (pinfunction "RF3_8") (pintype "passive"))
    )
    (net (code "54") (name "Net-(U304-RF4)") (class "Default")
      (node (ref "R325") (pin "1") (pinfunction "1_1") (pintype "passive"))
      (node (ref "R326") (pin "2") (pinfunction "2_2") (pintype "passive"))
      (node (ref "U304") (pin "5") (pinfunction "RF4_5") (pintype "passive"))
    )
    (net (code "55") (name "Net-(U304-RFC)") (class "Default")
      (node (ref "L303") (pin "2") (pinfunction "2_2") (pintype "passive"))
      (node (ref "R346") (pin "2") (pinfunction "2_2") (pintype "passive"))
      (node (ref "U304") (pin "22") (pinfunction "RFC_22") (pintype "passive"))
    )
    (net (code "56") (name "Net-(U305-RF1)") (class "Default")
      (node (ref "R328") (pin "1") (pinfunction "1_1") (pintype "passive"))
      (node (ref "R329") (pin "2") (pinfunction "2_2") (pintype "passive"))
      (node (ref "U305") (pin "14") (pinfunction "RF1_14") (pintype "passive"))
    )
    (net (code "57") (name "Net-(U305-RF2)") (class "Default")
      (node (ref "R331") (pin "1") (pinfunction "1_1") (pintype "passive"))
      (node (ref "R332") (pin "2") (pinfunction "2_2") (pintype "passive"))
      (node (ref "U305") (pin "11") (pinfunction "RF2_11") (pintype "passive"))
    )
    (net (code "58") (name "Net-(U305-RF3)") (class "Default")
      (node (ref "R340") (pin "1") (pinfunction "1_1") (pintype "passive"))
      (node (ref "U305") (pin "8") (pinfunction "RF3_8") (pintype "passive"))
    )
    (net (code "59") (name "Net-(U305-RF4)") (class "Default")
      (node (ref "R334") (pin "1") (pinfunction "1_1") (pintype "passive"))
      (node (ref "R335") (pin "2") (pinfunction "2_2") (pintype "passive"))
      (node (ref "U305") (pin "5") (pinfunction "RF4_5") (pintype "passive"))
    )
    (net (code "60") (name "Net-(U305-RFC)") (class "Default")
      (node (ref "L304") (pin "2") (pinfunction "2_2") (pintype "passive"))
      (node (ref "R348") (pin "2") (pinfunction "2_2") (pintype "passive"))
      (node (ref "U305") (pin "22") (pinfunction "RFC_22") (pintype "passive"))
    )
  )
)
